# atmega328.net
KiCad netlist of a schematic drawn in EAGLE
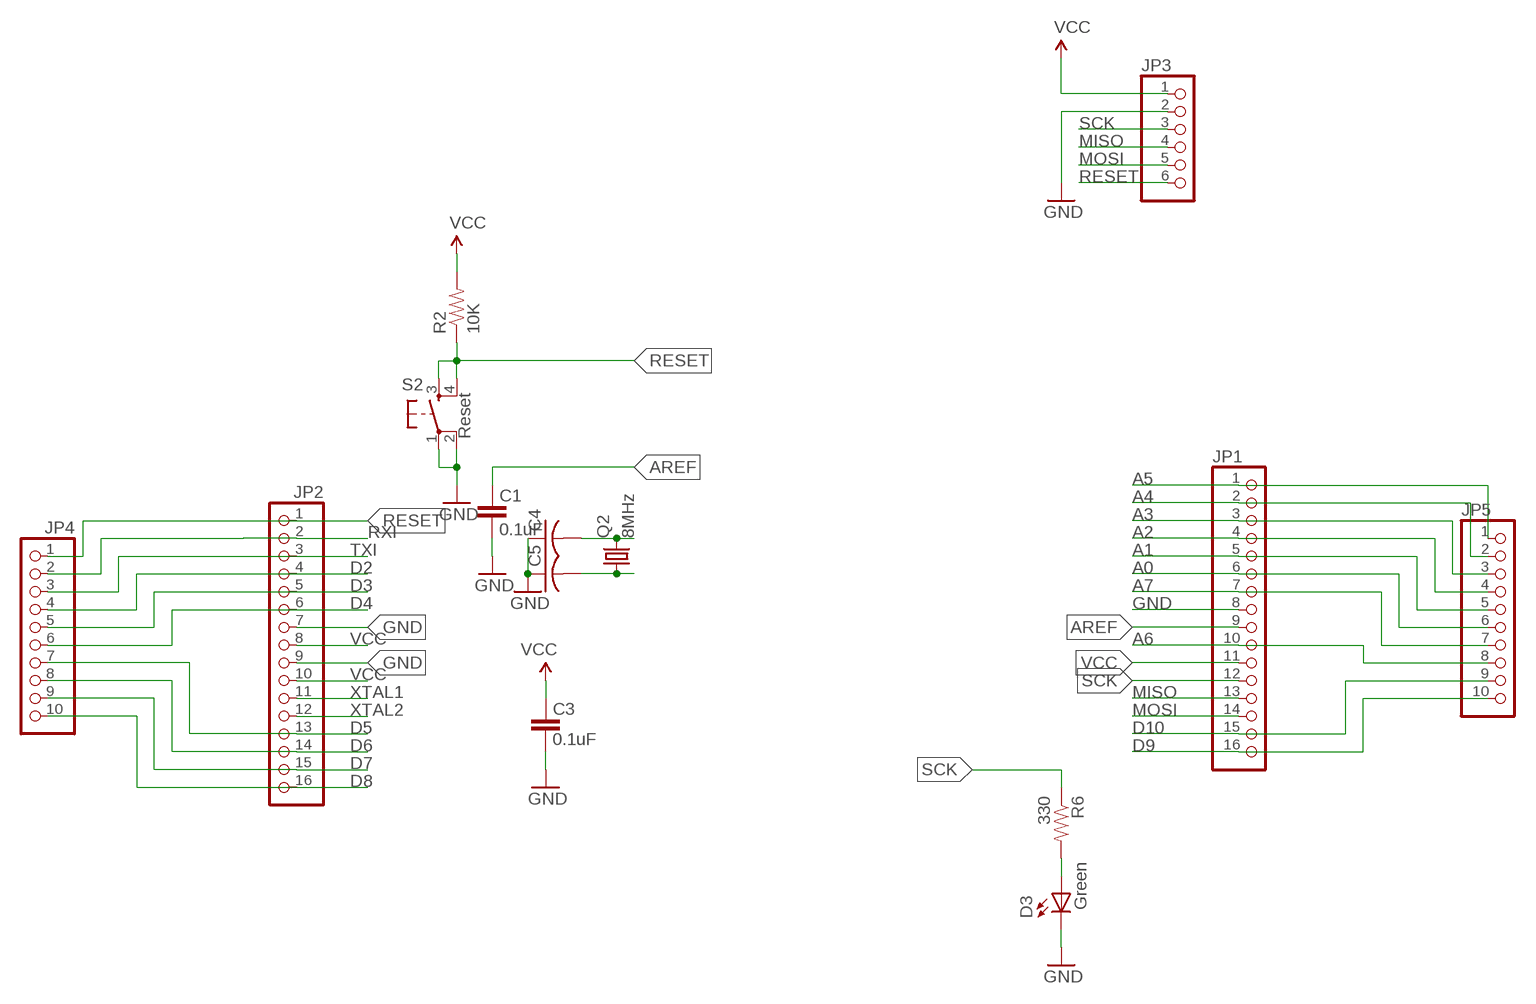
[diagram p0: schematic, sheet 1]

(export (version "E")
  (design (tool "Eeschema 10.0.6"))
  (components
    (comp (ref "C1")
      (value "0.1uF")
      (footprint "eagle-import:0805")
      (libsource (lib "eagle-import") (part "CAP0805"))
    )
    (comp (ref "C3")
      (value "0.1uF")
      (footprint "eagle-import:0805")
      (libsource (lib "eagle-import") (part "CAP0805"))
    )
    (comp (ref "C4")
      (value "C-USC0805")
      (footprint "eagle-import:C0805")
      (libsource (lib "eagle-import") (part "C-USC0805"))
    )
    (comp (ref "C5")
      (value "C-USC0805")
      (footprint "eagle-import:C0805")
      (libsource (lib "eagle-import") (part "C-USC0805"))
    )
    (comp (ref "D3")
      (value "Green")
      (footprint "eagle-import:LED-0603")
      (libsource (lib "eagle-import") (part "LED0603"))
    )
    (comp (ref "JP1")
      (value "PINHD-1X16")
      (footprint "eagle-import:1X16")
      (libsource (lib "eagle-import") (part "PINHD-1X16"))
    )
    (comp (ref "JP2")
      (value "PINHD-1X16")
      (footprint "eagle-import:1X16")
      (libsource (lib "eagle-import") (part "PINHD-1X16"))
    )
    (comp (ref "JP3")
      (value "PINHD-1X6")
      (footprint "eagle-import:1X06")
      (libsource (lib "eagle-import") (part "PINHD-1X6"))
    )
    (comp (ref "JP4")
      (value "PINHD-1X10")
      (footprint "eagle-import:1X10")
      (libsource (lib "eagle-import") (part "PINHD-1X10"))
    )
    (comp (ref "JP5")
      (value "PINHD-1X10")
      (footprint "eagle-import:1X10")
      (libsource (lib "eagle-import") (part "PINHD-1X10"))
    )
    (comp (ref "Q2")
      (value "8MHz")
      (footprint "eagle-import:CTS406")
      (libsource (lib "eagle-import") (part "CRYSTALCTS406"))
    )
    (comp (ref "R2")
      (value "10K")
      (footprint "eagle-import:0805")
      (libsource (lib "eagle-import") (part "RESISTOR"))
    )
    (comp (ref "R6")
      (value "330")
      (footprint "eagle-import:0805")
      (libsource (lib "eagle-import") (part "RESISTOR"))
    )
    (comp (ref "S2")
      (value "Reset")
      (footprint "eagle-import:TACTILE_SWITCH_SMD")
      (libsource (lib "eagle-import") (part "TAC_SWITCHSMD"))
    )
  )
  (nets
    (net (code "1") (name "/A0") (class "Default")
      (node (ref "JP1") (pin "6") (pinfunction "6_6") (pintype "passive"))
      (node (ref "JP5") (pin "6") (pinfunction "6_6") (pintype "passive"))
    )
    (net (code "2") (name "/A1") (class "Default")
      (node (ref "JP1") (pin "5") (pinfunction "5_5") (pintype "passive"))
      (node (ref "JP5") (pin "5") (pinfunction "5_5") (pintype "passive"))
    )
    (net (code "3") (name "/A2") (class "Default")
      (node (ref "JP1") (pin "4") (pinfunction "4_4") (pintype "passive"))
      (node (ref "JP5") (pin "4") (pinfunction "4_4") (pintype "passive"))
    )
    (net (code "4") (name "/A3") (class "Default")
      (node (ref "JP1") (pin "3") (pinfunction "3_3") (pintype "passive"))
      (node (ref "JP5") (pin "3") (pinfunction "3_3") (pintype "passive"))
    )
    (net (code "5") (name "/A4") (class "Default")
      (node (ref "JP1") (pin "2") (pinfunction "2_2") (pintype "passive"))
      (node (ref "JP5") (pin "2") (pinfunction "2_2") (pintype "passive"))
    )
    (net (code "6") (name "/A5") (class "Default")
      (node (ref "JP1") (pin "1") (pinfunction "1_1") (pintype "passive"))
      (node (ref "JP5") (pin "1") (pinfunction "1_1") (pintype "passive"))
    )
    (net (code "7") (name "/A6") (class "Default")
      (node (ref "JP1") (pin "10") (pinfunction "10_10") (pintype "passive"))
      (node (ref "JP5") (pin "8") (pinfunction "8_8") (pintype "passive"))
    )
    (net (code "8") (name "/A7") (class "Default")
      (node (ref "JP1") (pin "7") (pinfunction "7_7") (pintype "passive"))
      (node (ref "JP5") (pin "7") (pinfunction "7_7") (pintype "passive"))
    )
    (net (code "9") (name "/D2") (class "Default")
      (node (ref "JP2") (pin "4") (pinfunction "4_4") (pintype "passive"))
      (node (ref "JP4") (pin "4") (pinfunction "4_4") (pintype "passive"))
    )
    (net (code "10") (name "/D3") (class "Default")
      (node (ref "JP2") (pin "5") (pinfunction "5_5") (pintype "passive"))
      (node (ref "JP4") (pin "5") (pinfunction "5_5") (pintype "passive"))
    )
    (net (code "11") (name "/D4") (class "Default")
      (node (ref "JP2") (pin "6") (pinfunction "6_6") (pintype "passive"))
      (node (ref "JP4") (pin "6") (pinfunction "6_6") (pintype "passive"))
    )
    (net (code "12") (name "/D5") (class "Default")
      (node (ref "JP2") (pin "13") (pinfunction "13_13") (pintype "passive"))
      (node (ref "JP4") (pin "7") (pinfunction "7_7") (pintype "passive"))
    )
    (net (code "13") (name "/D6") (class "Default")
      (node (ref "JP2") (pin "14") (pinfunction "14_14") (pintype "passive"))
      (node (ref "JP4") (pin "8") (pinfunction "8_8") (pintype "passive"))
    )
    (net (code "14") (name "/D7") (class "Default")
      (node (ref "JP2") (pin "15") (pinfunction "15_15") (pintype "passive"))
      (node (ref "JP4") (pin "9") (pinfunction "9_9") (pintype "passive"))
    )
    (net (code "15") (name "/D8") (class "Default")
      (node (ref "JP2") (pin "16") (pinfunction "16_16") (pintype "passive"))
      (node (ref "JP4") (pin "10") (pinfunction "10_10") (pintype "passive"))
    )
    (net (code "16") (name "/D9") (class "Default")
      (node (ref "JP1") (pin "16") (pinfunction "16_16") (pintype "passive"))
      (node (ref "JP5") (pin "10") (pinfunction "10_10") (pintype "passive"))
    )
    (net (code "17") (name "/D10") (class "Default")
      (node (ref "JP1") (pin "15") (pinfunction "15_15") (pintype "passive"))
      (node (ref "JP5") (pin "9") (pinfunction "9_9") (pintype "passive"))
    )
    (net (code "18") (name "/MISO") (class "Default")
      (node (ref "JP1") (pin "13") (pinfunction "13_13") (pintype "passive"))
      (node (ref "JP3") (pin "4") (pinfunction "4_4") (pintype "passive"))
    )
    (net (code "19") (name "/MOSI") (class "Default")
      (node (ref "JP1") (pin "14") (pinfunction "14_14") (pintype "passive"))
      (node (ref "JP3") (pin "5") (pinfunction "5_5") (pintype "passive"))
    )
    (net (code "20") (name "/RXI") (class "Default")
      (node (ref "JP2") (pin "2") (pinfunction "2_2") (pintype "passive"))
      (node (ref "JP4") (pin "2") (pinfunction "2_2") (pintype "passive"))
    )
    (net (code "21") (name "/TXI") (class "Default")
      (node (ref "JP2") (pin "3") (pinfunction "3_3") (pintype "passive"))
      (node (ref "JP4") (pin "3") (pinfunction "3_3") (pintype "passive"))
    )
    (net (code "22") (name "/XTAL1") (class "Default")
      (node (ref "C4") (pin "2") (pinfunction "2_2") (pintype "passive"))
      (node (ref "JP2") (pin "11") (pinfunction "11_11") (pintype "passive"))
      (node (ref "Q2") (pin "3") (pinfunction "2_3") (pintype "passive"))
    )
    (net (code "23") (name "/XTAL2") (class "Default")
      (node (ref "C5") (pin "2") (pinfunction "2_2") (pintype "passive"))
      (node (ref "JP2") (pin "12") (pinfunction "12_12") (pintype "passive"))
      (node (ref "Q2") (pin "1") (pinfunction "1_1") (pintype "passive"))
    )
    (net (code "24") (name "AREF") (class "Default")
      (node (ref "C1") (pin "2") (pinfunction "2_2") (pintype "passive"))
      (node (ref "JP1") (pin "9") (pinfunction "9_9") (pintype "passive"))
    )
    (net (code "25") (name "GND") (class "Default")
      (node (ref "C1") (pin "1") (pinfunction "1_1") (pintype "passive"))
      (node (ref "C3") (pin "1") (pinfunction "1_1") (pintype "passive"))
      (node (ref "C4") (pin "1") (pinfunction "1_1") (pintype "passive"))
      (node (ref "C5") (pin "1") (pinfunction "1_1") (pintype "passive"))
      (node (ref "D3") (pin "C") (pinfunction "C_C") (pintype "passive"))
      (node (ref "JP1") (pin "8") (pinfunction "8_8") (pintype "passive"))
      (node (ref "JP2") (pin "7") (pinfunction "7_7") (pintype "passive"))
      (node (ref "JP2") (pin "9") (pinfunction "9_9") (pintype "passive"))
      (node (ref "JP3") (pin "2") (pinfunction "2_2") (pintype "passive"))
      (node (ref "S2") (pin "1") (pinfunction "1_1") (pintype "passive"))
      (node (ref "S2") (pin "2") (pinfunction "2_2") (pintype "passive"))
    )
    (net (code "26") (name "Net-(D3-PadA)") (class "Default")
      (node (ref "D3") (pin "A") (pinfunction "A_A") (pintype "passive"))
      (node (ref "R6") (pin "2") (pinfunction "2_2") (pintype "passive"))
    )
    (net (code "27") (name "RESET") (class "Default")
      (node (ref "JP2") (pin "1") (pinfunction "1_1") (pintype "passive"))
      (node (ref "JP3") (pin "6") (pinfunction "6_6") (pintype "passive"))
      (node (ref "JP4") (pin "1") (pinfunction "1_1") (pintype "passive"))
      (node (ref "R2") (pin "1") (pinfunction "1_1") (pintype "passive"))
      (node (ref "S2") (pin "3") (pinfunction "3_3") (pintype "passive"))
      (node (ref "S2") (pin "4") (pinfunction "4_4") (pintype "passive"))
    )
    (net (code "28") (name "SCK") (class "Default")
      (node (ref "JP1") (pin "12") (pinfunction "12_12") (pintype "passive"))
      (node (ref "JP3") (pin "3") (pinfunction "3_3") (pintype "passive"))
      (node (ref "R6") (pin "1") (pinfunction "1_1") (pintype "passive"))
    )
    (net (code "29") (name "VCC") (class "Default")
      (node (ref "C3") (pin "2") (pinfunction "2_2") (pintype "passive"))
      (node (ref "JP1") (pin "11") (pinfunction "11_11") (pintype "passive"))
      (node (ref "JP2") (pin "10") (pinfunction "10_10") (pintype "passive"))
      (node (ref "JP2") (pin "8") (pinfunction "8_8") (pintype "passive"))
      (node (ref "JP3") (pin "1") (pinfunction "1_1") (pintype "passive"))
      (node (ref "R2") (pin "2") (pinfunction "2_2") (pintype "passive"))
    )
  )
)
